# USB.net
KiCad netlist of a schematic drawn in Altium Designer
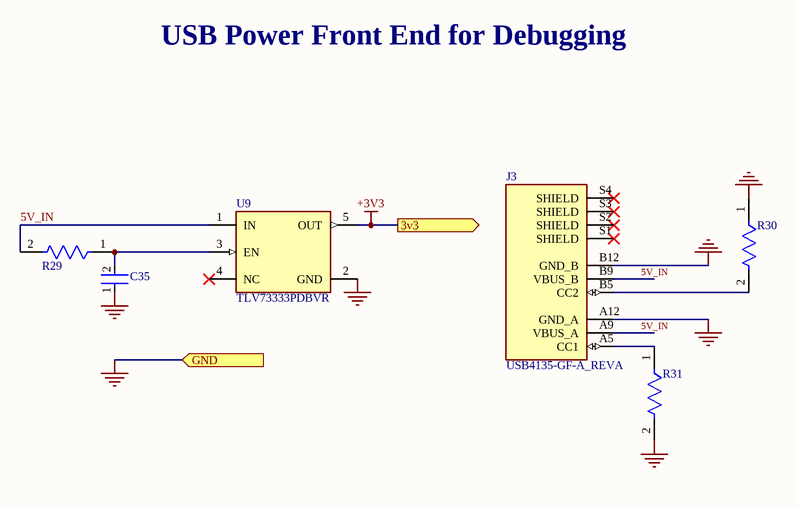
[diagram p0: USB.SchDoc]

(export (version "E")
  (design (tool "Eeschema 10.0.6"))
  (components
    (comp (ref "C35")
      (value "C1608X5R1H105K080AB")
      (footprint "FP-C1608-080-0_1-IPC_B")
      (description "Multilayer Ceramic Capacitors 1μF ±10% 50V X5R SMD 0603")
      (fields (field (name "VOLTAGE") "50V") (field (name "TOLERANCE") "10%"))
      (libsource (lib "Altium Content Vault") (part "236180d848d6139a670b325ea6854c9"))
    )
    (comp (ref "J3")
      (value "USB4135-GF-A_REVA")
      (footprint "GCT_USB4135-GF-A_REVA")
      (fields (field (name "MF") "Global Connector Technology") (field (name "MP") "USB4135GFA"))
      (libsource (lib "USB4135-GF-A_REVA") (part "USB4135-GF-A_REVA"))
    )
    (comp (ref "R29")
      (value "RC0603FR-0710KL")
      (footprint "FP-RC0603-0_55-IPC_C")
      (description "RES 10K OHM 1% 1/10W 0603")
      (fields (field (name "TOLERANCE") "1%"))
      (libsource (lib "Altium Content Vault") (part "1029c3af85768c4190bb7ad29bc67b5"))
    )
    (comp (ref "R30")
      (value "CRCW06035K10FKEA")
      (footprint "FP-CRCW0603-e3-IPC_C")
      (description "RES Thick Film, 5.1kΩ, 1%, 0.1W, 100ppm/°C, 0603")
      (fields (field (name "TOLERANCE") "1%"))
      (libsource (lib "Altium Content Vault") (part "1029c3af85768c4190bb7ad29bc67b5"))
    )
    (comp (ref "R31")
      (value "CRCW06035K10FKEA")
      (footprint "FP-CRCW0603-e3-IPC_C")
      (description "RES Thick Film, 5.1kΩ, 1%, 0.1W, 100ppm/°C, 0603")
      (fields (field (name "TOLERANCE") "1%"))
      (libsource (lib "Altium Content Vault") (part "1029c3af85768c4190bb7ad29bc67b5"))
    )
    (comp (ref "U9")
      (value "TLV73333PDBVR")
      (footprint "FP-DBV0005A-MFG")
      (description "IC REG LINEAR 3.3V 300MA SOT23-5")
      (fields
        (field (name "MANUFACTURER") "Texas Instruments")
        (field (name "OCTOPART") "https://octopart.com/tlv73333pdbvr-texas+instruments-51080890")
      )
      (libsource (lib "Altium Content Vault") (part "10cdd6a861ce8db355dac0efc8b397e"))
    )
  )
  (nets
    (net (code "1") (name "+3V3") (class "Default")
      (node (ref "U9") (pin "5") (pinfunction "OUT_5") (pintype "output"))
    )
    (net (code "2") (name "/5V_IN") (class "Default")
      (node (ref "J3") (pin "A9") (pinfunction "VBUS_A_A9") (pintype "power_in"))
      (node (ref "J3") (pin "B9") (pinfunction "VBUS_B_B9") (pintype "power_in"))
      (node (ref "R29") (pin "2") (pinfunction "2_2") (pintype "passive"))
      (node (ref "U9") (pin "1") (pinfunction "IN_1") (pintype "power_in"))
    )
    (net (code "3") (name "GND") (class "Default")
      (node (ref "C35") (pin "1") (pinfunction "1_1") (pintype "passive"))
      (node (ref "J3") (pin "A12") (pinfunction "GND_A_A12") (pintype "power_in"))
      (node (ref "J3") (pin "B12") (pinfunction "GND_B_B12") (pintype "power_in"))
      (node (ref "R30") (pin "1") (pinfunction "1_1") (pintype "passive"))
      (node (ref "R31") (pin "2") (pinfunction "2_2") (pintype "passive"))
      (node (ref "U9") (pin "2") (pinfunction "GND_2") (pintype "power_in"))
    )
    (net (code "4") (name "Net-(J3-CC1)") (class "Default")
      (node (ref "J3") (pin "A5") (pinfunction "CC1_A5") (pintype "bidirectional"))
      (node (ref "R31") (pin "1") (pinfunction "1_1") (pintype "passive"))
    )
    (net (code "5") (name "Net-(J3-CC2)") (class "Default")
      (node (ref "J3") (pin "B5") (pinfunction "CC2_B5") (pintype "bidirectional"))
      (node (ref "R30") (pin "2") (pinfunction "2_2") (pintype "passive"))
    )
    (net (code "6") (name "Net-(U9-EN)") (class "Default")
      (node (ref "C35") (pin "2") (pinfunction "2_2") (pintype "passive"))
      (node (ref "R29") (pin "1") (pinfunction "1_1") (pintype "passive"))
      (node (ref "U9") (pin "3") (pinfunction "EN_3") (pintype "input"))
    )
    (net (code "7") (name "unconnected-(J3-SHIELD-PadS1)") (class "Default")
      (node (ref "J3") (pin "S1") (pinfunction "SHIELD_S1") (pintype "passive+no_connect"))
    )
    (net (code "8") (name "unconnected-(J3-SHIELD-PadS2)") (class "Default")
      (node (ref "J3") (pin "S2") (pinfunction "SHIELD_S2") (pintype "passive+no_connect"))
    )
    (net (code "9") (name "unconnected-(J3-SHIELD-PadS3)") (class "Default")
      (node (ref "J3") (pin "S3") (pinfunction "SHIELD_S3") (pintype "passive+no_connect"))
    )
    (net (code "10") (name "unconnected-(J3-SHIELD-PadS4)") (class "Default")
      (node (ref "J3") (pin "S4") (pinfunction "SHIELD_S4") (pintype "passive+no_connect"))
    )
    (net (code "11") (name "unconnected-(U9-NC-Pad4)") (class "Default")
      (node (ref "U9") (pin "4") (pinfunction "NC_4") (pintype "passive+no_connect"))
    )
  )
)
